# 3_W5500Net.net
KiCad netlist of a schematic drawn in Altium Designer
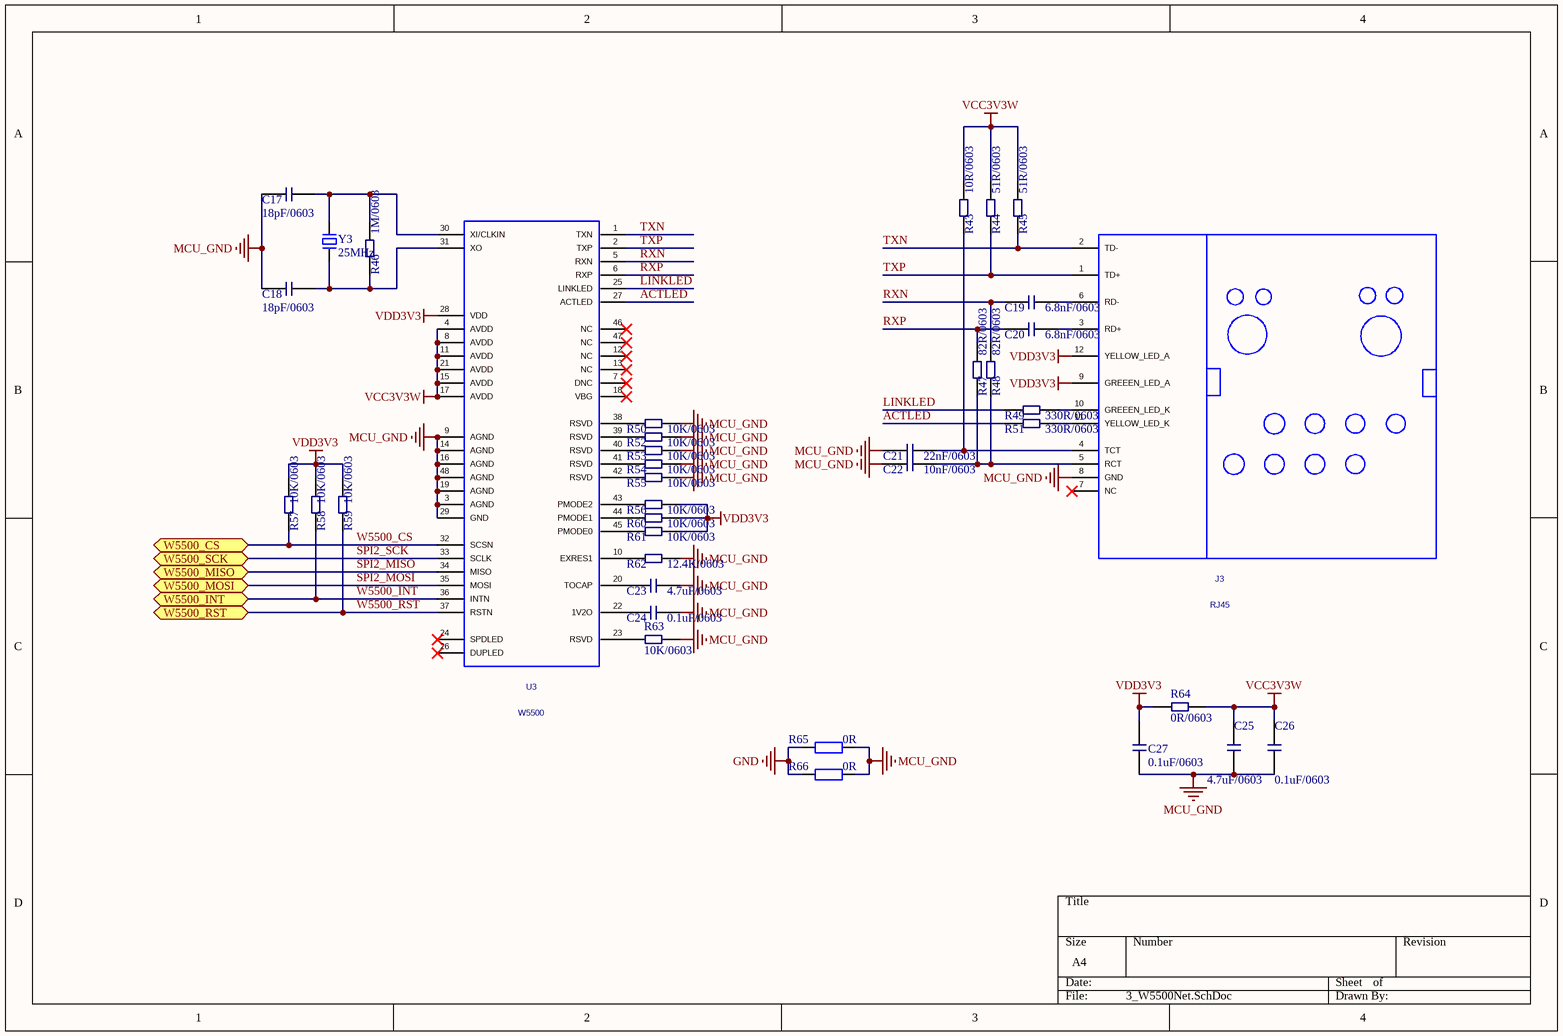
[diagram p0: 3_W5500Net.SchDoc]

(export (version "E")
  (design (tool "Eeschema 10.0.6"))
  (components
    (comp (ref "C17")
      (value "18pF/0603")
      (footprint "LC-0603_C")
      (libsource (lib "SWUST_PanPan") (part "CAP-0603"))
    )
    (comp (ref "C18")
      (value "18pF/0603")
      (footprint "LC-0603_C")
      (libsource (lib "SWUST_PanPan") (part "CAP-0603"))
    )
    (comp (ref "C19")
      (value "6.8nF/0603")
      (footprint "LC-0603_C")
      (libsource (lib "SWUST_PanPan") (part "CAP-0603"))
    )
    (comp (ref "C20")
      (value "6.8nF/0603")
      (footprint "LC-0603_C")
      (libsource (lib "SWUST_PanPan") (part "CAP-0603"))
    )
    (comp (ref "C21")
      (value "22nF/0603")
      (footprint "LC-0603_C")
      (libsource (lib "SWUST_PanPan") (part "CAP-0603"))
    )
    (comp (ref "C22")
      (value "10nF/0603")
      (footprint "LC-0603_C")
      (libsource (lib "SWUST_PanPan") (part "CAP-0603"))
    )
    (comp (ref "C23")
      (value "4.7uF/0603")
      (footprint "LC-0603_C")
      (libsource (lib "SWUST_PanPan") (part "CAP-0603"))
    )
    (comp (ref "C24")
      (value "0.1uF/0603")
      (footprint "LC-0603_C")
      (libsource (lib "SWUST_PanPan") (part "CAP-0603"))
    )
    (comp (ref "C25")
      (value "4.7uF/0603")
      (footprint "LC-0603_C")
      (libsource (lib "SWUST_PanPan") (part "CAP-0603"))
    )
    (comp (ref "C26")
      (value "0.1uF/0603")
      (footprint "LC-0603_C")
      (libsource (lib "SWUST_PanPan") (part "CAP-0603"))
    )
    (comp (ref "C27")
      (value "0.1uF/0603")
      (footprint "LC-0603_C")
      (libsource (lib "SWUST_PanPan") (part "CAP-0603"))
    )
    (comp (ref "J3") (value "RJ45") (footprint "RJ-45A12") (libsource (lib "ISO-V3") (part "RJ45")))
    (comp (ref "R43")
      (value "10R/0603")
      (footprint "LC-0603_R")
      (libsource (lib "SWUST_PanPan") (part "RES-0603"))
    )
    (comp (ref "R44")
      (value "51R/0603")
      (footprint "LC-0603_R")
      (libsource (lib "SWUST_PanPan") (part "RES-0603"))
    )
    (comp (ref "R45")
      (value "51R/0603")
      (footprint "LC-0603_R")
      (libsource (lib "SWUST_PanPan") (part "RES-0603"))
    )
    (comp (ref "R46")
      (value "1M/0603")
      (footprint "LC-0603_R")
      (libsource (lib "SWUST_PanPan") (part "RES-0603"))
    )
    (comp (ref "R47")
      (value "82R/0603")
      (footprint "LC-0603_R")
      (libsource (lib "SWUST_PanPan") (part "RES-0603"))
    )
    (comp (ref "R48")
      (value "82R/0603")
      (footprint "LC-0603_R")
      (libsource (lib "SWUST_PanPan") (part "RES-0603"))
    )
    (comp (ref "R49")
      (value "330R/0603")
      (footprint "LC-0603_R")
      (libsource (lib "SWUST_PanPan") (part "RES-0603"))
    )
    (comp (ref "R50")
      (value "10K/0603")
      (footprint "LC-0603_R")
      (libsource (lib "SWUST_PanPan") (part "RES-0603"))
    )
    (comp (ref "R51")
      (value "330R/0603")
      (footprint "LC-0603_R")
      (libsource (lib "SWUST_PanPan") (part "RES-0603"))
    )
    (comp (ref "R52")
      (value "10K/0603")
      (footprint "LC-0603_R")
      (libsource (lib "SWUST_PanPan") (part "RES-0603"))
    )
    (comp (ref "R53")
      (value "10K/0603")
      (footprint "LC-0603_R")
      (libsource (lib "SWUST_PanPan") (part "RES-0603"))
    )
    (comp (ref "R54")
      (value "10K/0603")
      (footprint "LC-0603_R")
      (libsource (lib "SWUST_PanPan") (part "RES-0603"))
    )
    (comp (ref "R55")
      (value "10K/0603")
      (footprint "LC-0603_R")
      (libsource (lib "SWUST_PanPan") (part "RES-0603"))
    )
    (comp (ref "R56")
      (value "10K/0603")
      (footprint "LC-0603_R")
      (libsource (lib "SWUST_PanPan") (part "RES-0603"))
    )
    (comp (ref "R57")
      (value "10K/0603")
      (footprint "LC-0603_R")
      (libsource (lib "SWUST_PanPan") (part "RES-0603"))
    )
    (comp (ref "R58")
      (value "10K/0603")
      (footprint "LC-0603_R")
      (libsource (lib "SWUST_PanPan") (part "RES-0603"))
    )
    (comp (ref "R59")
      (value "10K/0603")
      (footprint "LC-0603_R")
      (libsource (lib "SWUST_PanPan") (part "RES-0603"))
    )
    (comp (ref "R60")
      (value "10K/0603")
      (footprint "LC-0603_R")
      (libsource (lib "SWUST_PanPan") (part "RES-0603"))
    )
    (comp (ref "R61")
      (value "10K/0603")
      (footprint "LC-0603_R")
      (libsource (lib "SWUST_PanPan") (part "RES-0603"))
    )
    (comp (ref "R62")
      (value "12.4K/0603")
      (footprint "LC-0603_R")
      (libsource (lib "SWUST_PanPan") (part "RES-0603"))
    )
    (comp (ref "R63")
      (value "10K/0603")
      (footprint "LC-0603_R")
      (libsource (lib "SWUST_PanPan") (part "RES-0603"))
    )
    (comp (ref "R64")
      (value "0R/0603")
      (footprint "LC-0603_R")
      (libsource (lib "SWUST_PanPan") (part "RES-0603"))
    )
    (comp (ref "R65")
      (value "0R")
      (footprint "LC-0603_R")
      (description "贴片电阻")
      (fields (field (name "PUBLISHER") "Altium Limited"))
      (libsource (lib "liu_2016") (part "Res1"))
    )
    (comp (ref "R66")
      (value "0R")
      (footprint "LC-0603_R")
      (description "贴片电阻")
      (fields (field (name "PUBLISHER") "Altium Limited"))
      (libsource (lib "liu_2016") (part "Res1"))
    )
    (comp (ref "U3") (value "W5500") (footprint "LQFP48-7*7") (libsource (lib "ISO-V3") (part "W5500")))
    (comp (ref "Y3")
      (value "25MHz")
      (footprint "OSC HC-49S")
      (description "2脚无源脚晶振")
      (fields (field (name "版权归属") "源创客"))
      (libsource (lib "10.1 - 保险丝-晶振") (part "XTAL-2P"))
    )
  )
  (nets
    (net (code "1") (name "/ACTLED") (class "Default")
      (node (ref "R51") (pin "1") (pinfunction "1_1") (pintype "passive"))
      (node (ref "U3") (pin "27") (pinfunction "ACTLED_27") (pintype "passive"))
    )
    (net (code "2") (name "/LINKLED") (class "Default")
      (node (ref "R49") (pin "1") (pinfunction "1_1") (pintype "passive"))
      (node (ref "U3") (pin "25") (pinfunction "LINKLED_25") (pintype "passive"))
    )
    (net (code "3") (name "/RXN") (class "Default")
      (node (ref "C19") (pin "1") (pinfunction "1_1") (pintype "passive"))
      (node (ref "R48") (pin "2") (pinfunction "2_2") (pintype "passive"))
      (node (ref "U3") (pin "5") (pinfunction "RXN_5") (pintype "passive"))
    )
    (net (code "4") (name "/RXP") (class "Default")
      (node (ref "C20") (pin "1") (pinfunction "1_1") (pintype "passive"))
      (node (ref "R47") (pin "2") (pinfunction "2_2") (pintype "passive"))
      (node (ref "U3") (pin "6") (pinfunction "RXP_6") (pintype "passive"))
    )
    (net (code "5") (name "/SPI2_MISO") (class "Default")
      (node (ref "U3") (pin "34") (pinfunction "MISO_34") (pintype "passive"))
    )
    (net (code "6") (name "/SPI2_MOSI") (class "Default")
      (node (ref "U3") (pin "35") (pinfunction "MOSI_35") (pintype "passive"))
    )
    (net (code "7") (name "/SPI2_SCK") (class "Default")
      (node (ref "U3") (pin "33") (pinfunction "SCLK_33") (pintype "passive"))
    )
    (net (code "8") (name "/TXN") (class "Default")
      (node (ref "J3") (pin "2") (pinfunction "TD-_2") (pintype "passive"))
      (node (ref "R45") (pin "1") (pinfunction "1_1") (pintype "passive"))
      (node (ref "U3") (pin "1") (pinfunction "TXN_1") (pintype "passive"))
    )
    (net (code "9") (name "/TXP") (class "Default")
      (node (ref "J3") (pin "1") (pinfunction "TD+_1") (pintype "passive"))
      (node (ref "R44") (pin "1") (pinfunction "1_1") (pintype "passive"))
      (node (ref "U3") (pin "2") (pinfunction "TXP_2") (pintype "passive"))
    )
    (net (code "10") (name "/W5500_CS") (class "Default")
      (node (ref "R57") (pin "2") (pinfunction "2_2") (pintype "passive"))
      (node (ref "U3") (pin "32") (pinfunction "SCSN_32") (pintype "passive"))
    )
    (net (code "11") (name "/W5500_INT") (class "Default")
      (node (ref "R58") (pin "2") (pinfunction "2_2") (pintype "passive"))
      (node (ref "U3") (pin "36") (pinfunction "INTN_36") (pintype "passive"))
    )
    (net (code "12") (name "/W5500_RST") (class "Default")
      (node (ref "R59") (pin "2") (pinfunction "2_2") (pintype "passive"))
      (node (ref "U3") (pin "37") (pinfunction "RSTN_37") (pintype "passive"))
    )
    (net (code "13") (name "GND") (class "Default")
      (node (ref "R65") (pin "2") (pinfunction "2_2") (pintype "passive"))
      (node (ref "R66") (pin "2") (pinfunction "2_2") (pintype "passive"))
    )
    (net (code "14") (name "MCU_GND") (class "Default")
      (node (ref "C17") (pin "1") (pinfunction "1_1") (pintype "passive"))
      (node (ref "C18") (pin "1") (pinfunction "1_1") (pintype "passive"))
      (node (ref "C21") (pin "1") (pinfunction "1_1") (pintype "passive"))
      (node (ref "C22") (pin "1") (pinfunction "1_1") (pintype "passive"))
      (node (ref "C23") (pin "2") (pinfunction "2_2") (pintype "passive"))
      (node (ref "C24") (pin "2") (pinfunction "2_2") (pintype "passive"))
      (node (ref "C25") (pin "1") (pinfunction "1_1") (pintype "passive"))
      (node (ref "C26") (pin "1") (pinfunction "1_1") (pintype "passive"))
      (node (ref "C27") (pin "1") (pinfunction "1_1") (pintype "passive"))
      (node (ref "J3") (pin "8") (pinfunction "GND_8") (pintype "passive"))
      (node (ref "R50") (pin "1") (pinfunction "1_1") (pintype "passive"))
      (node (ref "R52") (pin "1") (pinfunction "1_1") (pintype "passive"))
      (node (ref "R53") (pin "1") (pinfunction "1_1") (pintype "passive"))
      (node (ref "R54") (pin "1") (pinfunction "1_1") (pintype "passive"))
      (node (ref "R55") (pin "1") (pinfunction "1_1") (pintype "passive"))
      (node (ref "R62") (pin "2") (pinfunction "2_2") (pintype "passive"))
      (node (ref "R63") (pin "1") (pinfunction "1_1") (pintype "passive"))
      (node (ref "R65") (pin "1") (pinfunction "1_1") (pintype "passive"))
      (node (ref "R66") (pin "1") (pinfunction "1_1") (pintype "passive"))
      (node (ref "U3") (pin "14") (pinfunction "AGND_14") (pintype "passive"))
      (node (ref "U3") (pin "16") (pinfunction "AGND_16") (pintype "passive"))
      (node (ref "U3") (pin "19") (pinfunction "AGND_19") (pintype "passive"))
      (node (ref "U3") (pin "29") (pinfunction "GND_29") (pintype "passive"))
      (node (ref "U3") (pin "3") (pinfunction "AGND_3") (pintype "passive"))
      (node (ref "U3") (pin "48") (pinfunction "AGND_48") (pintype "passive"))
      (node (ref "U3") (pin "9") (pinfunction "AGND_9") (pintype "passive"))
    )
    (net (code "15") (name "Net-(J3-GREEEN_LED_K)") (class "Default")
      (node (ref "J3") (pin "10") (pinfunction "GREEEN_LED_K_10") (pintype "passive"))
      (node (ref "R49") (pin "2") (pinfunction "2_2") (pintype "passive"))
    )
    (net (code "16") (name "Net-(J3-RCT)") (class "Default")
      (node (ref "C22") (pin "2") (pinfunction "2_2") (pintype "passive"))
      (node (ref "J3") (pin "5") (pinfunction "RCT_5") (pintype "passive"))
      (node (ref "R47") (pin "1") (pinfunction "1_1") (pintype "passive"))
      (node (ref "R48") (pin "1") (pinfunction "1_1") (pintype "passive"))
    )
    (net (code "17") (name "Net-(J3-RD+)") (class "Default")
      (node (ref "C20") (pin "2") (pinfunction "2_2") (pintype "passive"))
      (node (ref "J3") (pin "3") (pinfunction "RD+_3") (pintype "passive"))
    )
    (net (code "18") (name "Net-(J3-RD-)") (class "Default")
      (node (ref "C19") (pin "2") (pinfunction "2_2") (pintype "passive"))
      (node (ref "J3") (pin "6") (pinfunction "RD-_6") (pintype "passive"))
    )
    (net (code "19") (name "Net-(J3-TCT)") (class "Default")
      (node (ref "C21") (pin "2") (pinfunction "2_2") (pintype "passive"))
      (node (ref "J3") (pin "4") (pinfunction "TCT_4") (pintype "passive"))
      (node (ref "R43") (pin "1") (pinfunction "1_1") (pintype "passive"))
    )
    (net (code "20") (name "Net-(J3-YELLOW_LED_K)") (class "Default")
      (node (ref "J3") (pin "11") (pinfunction "YELLOW_LED_K_11") (pintype "passive"))
      (node (ref "R51") (pin "2") (pinfunction "2_2") (pintype "passive"))
    )
    (net (code "21") (name "Net-(R50-Pad2)") (class "Default")
      (node (ref "R50") (pin "2") (pinfunction "2_2") (pintype "passive"))
      (node (ref "U3") (pin "38") (pinfunction "RSVD_38") (pintype "passive"))
    )
    (net (code "22") (name "Net-(R52-Pad2)") (class "Default")
      (node (ref "R52") (pin "2") (pinfunction "2_2") (pintype "passive"))
      (node (ref "U3") (pin "39") (pinfunction "RSVD_39") (pintype "passive"))
    )
    (net (code "23") (name "Net-(R53-Pad2)") (class "Default")
      (node (ref "R53") (pin "2") (pinfunction "2_2") (pintype "passive"))
      (node (ref "U3") (pin "40") (pinfunction "RSVD_40") (pintype "passive"))
    )
    (net (code "24") (name "Net-(R54-Pad2)") (class "Default")
      (node (ref "R54") (pin "2") (pinfunction "2_2") (pintype "passive"))
      (node (ref "U3") (pin "41") (pinfunction "RSVD_41") (pintype "passive"))
    )
    (net (code "25") (name "Net-(R55-Pad2)") (class "Default")
      (node (ref "R55") (pin "2") (pinfunction "2_2") (pintype "passive"))
      (node (ref "U3") (pin "42") (pinfunction "RSVD_42") (pintype "passive"))
    )
    (net (code "26") (name "Net-(R63-Pad2)") (class "Default")
      (node (ref "R63") (pin "2") (pinfunction "2_2") (pintype "passive"))
      (node (ref "U3") (pin "23") (pinfunction "RSVD_23") (pintype "passive"))
    )
    (net (code "27") (name "Net-(U3-1V2O)") (class "Default")
      (node (ref "C24") (pin "1") (pinfunction "1_1") (pintype "passive"))
      (node (ref "U3") (pin "22") (pinfunction "1V2O_22") (pintype "passive"))
    )
    (net (code "28") (name "Net-(U3-EXRES1)") (class "Default")
      (node (ref "R62") (pin "1") (pinfunction "1_1") (pintype "passive"))
      (node (ref "U3") (pin "10") (pinfunction "EXRES1_10") (pintype "passive"))
    )
    (net (code "29") (name "Net-(U3-PMODE0)") (class "Default")
      (node (ref "R61") (pin "2") (pinfunction "2_2") (pintype "passive"))
      (node (ref "U3") (pin "45") (pinfunction "PMODE0_45") (pintype "passive"))
    )
    (net (code "30") (name "Net-(U3-PMODE1)") (class "Default")
      (node (ref "R60") (pin "2") (pinfunction "2_2") (pintype "passive"))
      (node (ref "U3") (pin "44") (pinfunction "PMODE1_44") (pintype "passive"))
    )
    (net (code "31") (name "Net-(U3-PMODE2)") (class "Default")
      (node (ref "R56") (pin "2") (pinfunction "2_2") (pintype "passive"))
      (node (ref "U3") (pin "43") (pinfunction "PMODE2_43") (pintype "passive"))
    )
    (net (code "32") (name "Net-(U3-TOCAP)") (class "Default")
      (node (ref "C23") (pin "1") (pinfunction "1_1") (pintype "passive"))
      (node (ref "U3") (pin "20") (pinfunction "TOCAP_20") (pintype "passive"))
    )
    (net (code "33") (name "Net-(U3-XI{slash}CLKIN)") (class "Default")
      (node (ref "C17") (pin "2") (pinfunction "2_2") (pintype "passive"))
      (node (ref "R46") (pin "2") (pinfunction "2_2") (pintype "passive"))
      (node (ref "U3") (pin "30") (pinfunction "XI/CLKIN_30") (pintype "passive"))
      (node (ref "Y3") (pin "2") (pinfunction "2_2") (pintype "passive"))
    )
    (net (code "34") (name "Net-(U3-XO)") (class "Default")
      (node (ref "C18") (pin "2") (pinfunction "2_2") (pintype "passive"))
      (node (ref "R46") (pin "1") (pinfunction "1_1") (pintype "passive"))
      (node (ref "U3") (pin "31") (pinfunction "XO_31") (pintype "passive"))
      (node (ref "Y3") (pin "1") (pinfunction "1_1") (pintype "passive"))
    )
    (net (code "35") (name "VCC3V3W") (class "Default")
      (node (ref "C25") (pin "2") (pinfunction "2_2") (pintype "passive"))
      (node (ref "C26") (pin "2") (pinfunction "2_2") (pintype "passive"))
      (node (ref "R43") (pin "2") (pinfunction "2_2") (pintype "passive"))
      (node (ref "R44") (pin "2") (pinfunction "2_2") (pintype "passive"))
      (node (ref "R45") (pin "2") (pinfunction "2_2") (pintype "passive"))
      (node (ref "R64") (pin "2") (pinfunction "2_2") (pintype "passive"))
      (node (ref "U3") (pin "11") (pinfunction "AVDD_11") (pintype "passive"))
      (node (ref "U3") (pin "15") (pinfunction "AVDD_15") (pintype "passive"))
      (node (ref "U3") (pin "17") (pinfunction "AVDD_17") (pintype "passive"))
      (node (ref "U3") (pin "21") (pinfunction "AVDD_21") (pintype "passive"))
      (node (ref "U3") (pin "4") (pinfunction "AVDD_4") (pintype "passive"))
      (node (ref "U3") (pin "8") (pinfunction "AVDD_8") (pintype "passive"))
    )
    (net (code "36") (name "VDD3V3") (class "Default")
      (node (ref "C27") (pin "2") (pinfunction "2_2") (pintype "passive"))
      (node (ref "J3") (pin "12") (pinfunction "YELLOW_LED_A_12") (pintype "passive"))
      (node (ref "J3") (pin "9") (pinfunction "GREEEN_LED_A_9") (pintype "passive"))
      (node (ref "R56") (pin "1") (pinfunction "1_1") (pintype "passive"))
      (node (ref "R57") (pin "1") (pinfunction "1_1") (pintype "passive"))
      (node (ref "R58") (pin "1") (pinfunction "1_1") (pintype "passive"))
      (node (ref "R59") (pin "1") (pinfunction "1_1") (pintype "passive"))
      (node (ref "R60") (pin "1") (pinfunction "1_1") (pintype "passive"))
      (node (ref "R61") (pin "1") (pinfunction "1_1") (pintype "passive"))
      (node (ref "R64") (pin "1") (pinfunction "1_1") (pintype "passive"))
      (node (ref "U3") (pin "28") (pinfunction "VDD_28") (pintype "passive"))
    )
    (net (code "37") (name "unconnected-(J3-NC-Pad7)") (class "Default")
      (node (ref "J3") (pin "7") (pinfunction "NC_7") (pintype "passive+no_connect"))
    )
    (net (code "38") (name "unconnected-(U3-DNC-Pad7)") (class "Default")
      (node (ref "U3") (pin "7") (pinfunction "DNC_7") (pintype "passive+no_connect"))
    )
    (net (code "39") (name "unconnected-(U3-DUPLED-Pad26)") (class "Default")
      (node (ref "U3") (pin "26") (pinfunction "DUPLED_26") (pintype "passive+no_connect"))
    )
    (net (code "40") (name "unconnected-(U3-NC-Pad12)") (class "Default")
      (node (ref "U3") (pin "12") (pinfunction "NC_12") (pintype "passive+no_connect"))
    )
    (net (code "41") (name "unconnected-(U3-NC-Pad13)") (class "Default")
      (node (ref "U3") (pin "13") (pinfunction "NC_13") (pintype "passive+no_connect"))
    )
    (net (code "42") (name "unconnected-(U3-NC-Pad46)") (class "Default")
      (node (ref "U3") (pin "46") (pinfunction "NC_46") (pintype "passive+no_connect"))
    )
    (net (code "43") (name "unconnected-(U3-NC-Pad47)") (class "Default")
      (node (ref "U3") (pin "47") (pinfunction "NC_47") (pintype "passive+no_connect"))
    )
    (net (code "44") (name "unconnected-(U3-SPDLED-Pad24)") (class "Default")
      (node (ref "U3") (pin "24") (pinfunction "SPDLED_24") (pintype "passive+no_connect"))
    )
    (net (code "45") (name "unconnected-(U3-VBG-Pad18)") (class "Default")
      (node (ref "U3") (pin "18") (pinfunction "VBG_18") (pintype "passive+no_connect"))
    )
  )
)
